# Ethernet.net
KiCad netlist of a schematic drawn in Altium Designer
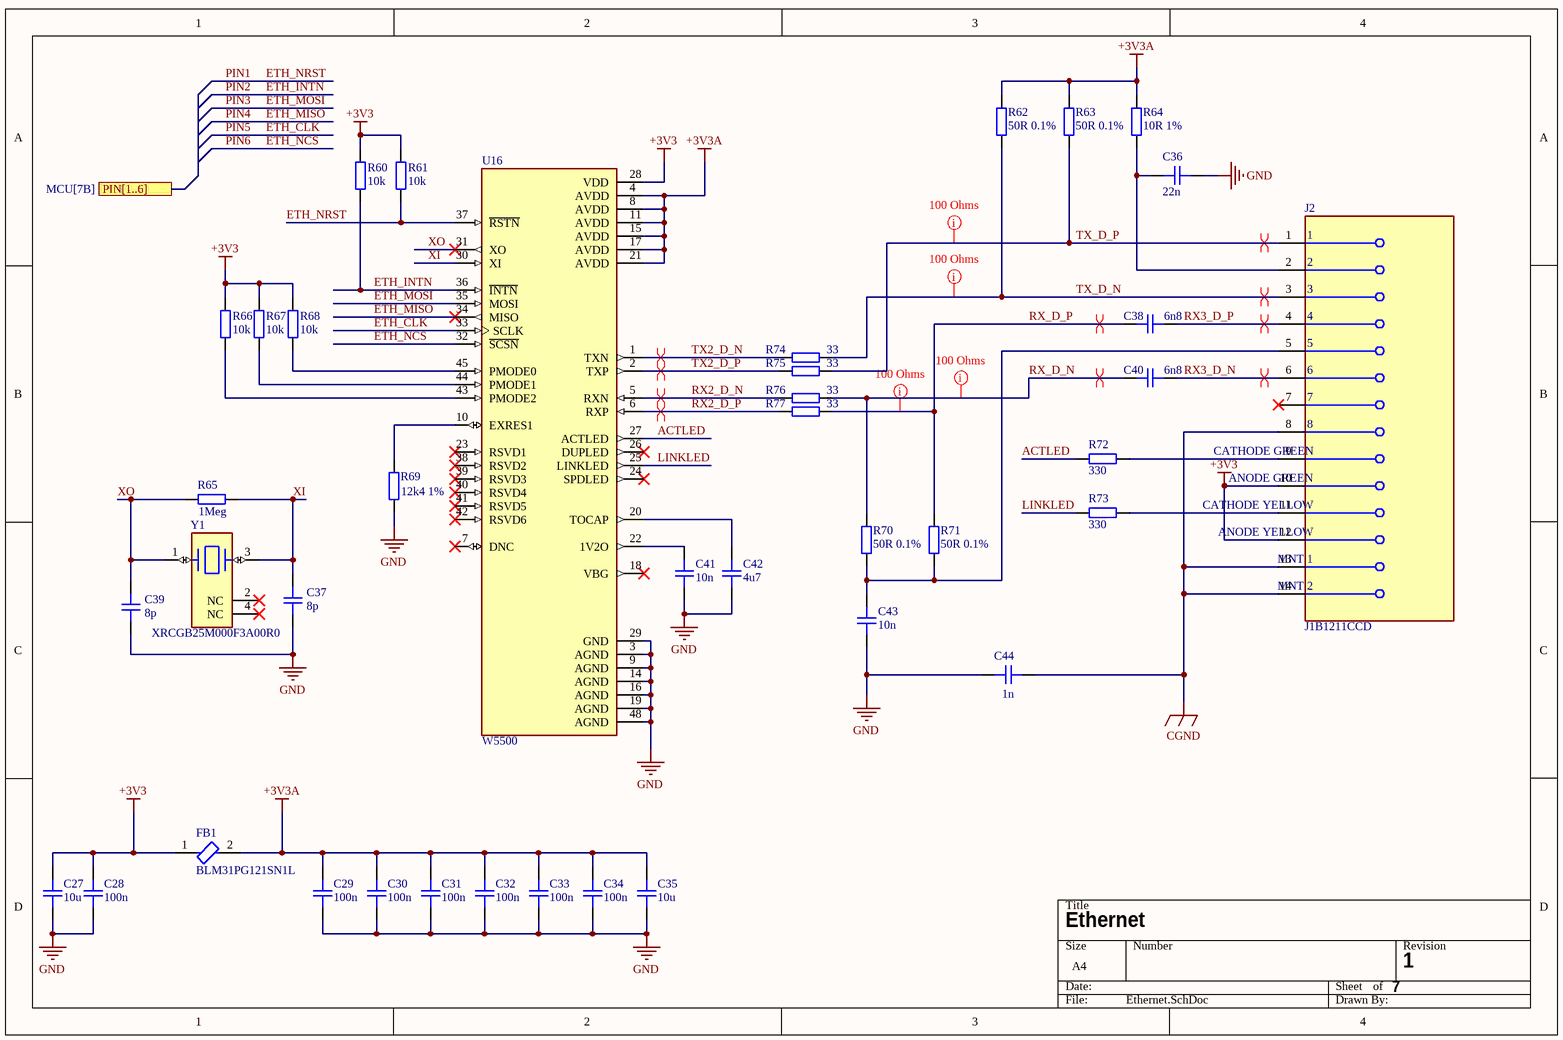
[diagram p0: Ethernet.SchDoc]

(export (version "E")
  (design (tool "Eeschema 10.0.6"))
  (components
    (comp (ref "C27")
      (value "10u")
      (footprint "CAP_0402")
      (description "Capacitor SMD 0402")
      (fields (field (name "Comment") "CL05A106MQ5NUNC"))
      (libsource (lib "Schematic-Lib-PhilsLab") (part "CAP_0402"))
    )
    (comp (ref "C28")
      (value "CL05B104KB54PNC")
      (footprint "CAP_0402")
      (description "Capacitor SMD 0402")
      (fields (field (name "RATING") "100n"))
      (libsource (lib "Schematic-Lib-PhilsLab") (part "CAP_0402"))
    )
    (comp (ref "C29")
      (value "CL05B104KB54PNC")
      (footprint "CAP_0402")
      (description "Capacitor SMD 0402")
      (fields (field (name "RATING") "100n"))
      (libsource (lib "Schematic-Lib-PhilsLab") (part "CAP_0402"))
    )
    (comp (ref "C30")
      (value "CL05B104KB54PNC")
      (footprint "CAP_0402")
      (description "Capacitor SMD 0402")
      (fields (field (name "RATING") "100n"))
      (libsource (lib "Schematic-Lib-PhilsLab") (part "CAP_0402"))
    )
    (comp (ref "C31")
      (value "CL05B104KB54PNC")
      (footprint "CAP_0402")
      (description "Capacitor SMD 0402")
      (fields (field (name "RATING") "100n"))
      (libsource (lib "Schematic-Lib-PhilsLab") (part "CAP_0402"))
    )
    (comp (ref "C32")
      (value "CL05B104KB54PNC")
      (footprint "CAP_0402")
      (description "Capacitor SMD 0402")
      (fields (field (name "RATING") "100n"))
      (libsource (lib "Schematic-Lib-PhilsLab") (part "CAP_0402"))
    )
    (comp (ref "C33")
      (value "CL05B104KB54PNC")
      (footprint "CAP_0402")
      (description "Capacitor SMD 0402")
      (fields (field (name "RATING") "100n"))
      (libsource (lib "Schematic-Lib-PhilsLab") (part "CAP_0402"))
    )
    (comp (ref "C34")
      (value "CL05B104KB54PNC")
      (footprint "CAP_0402")
      (description "Capacitor SMD 0402")
      (fields (field (name "RATING") "100n"))
      (libsource (lib "Schematic-Lib-PhilsLab") (part "CAP_0402"))
    )
    (comp (ref "C35")
      (value "10u")
      (footprint "CAP_0402")
      (description "Capacitor SMD 0402")
      (fields (field (name "Comment") "CL05A106MQ5NUNC"))
      (libsource (lib "Schematic-Lib-PhilsLab") (part "CAP_0402"))
    )
    (comp (ref "C36")
      (value "0402B223K500NT")
      (footprint "CAP_0402")
      (description "Capacitor SMD 0402")
      (fields (field (name "RATING") "22n"))
      (libsource (lib "Schematic-Lib-PhilsLab") (part "CAP_0402"))
    )
    (comp (ref "C37")
      (value "0402CG8R0C500NT")
      (footprint "CAP_0402")
      (description "Capacitor SMD 0402")
      (fields (field (name "RATING") "8p"))
      (libsource (lib "Schematic-Lib-PhilsLab") (part "CAP_0402"))
    )
    (comp (ref "C38")
      (value "0402B682K500NT")
      (footprint "CAP_0402")
      (description "Capacitor SMD 0402")
      (fields (field (name "RATING") "6n8"))
      (libsource (lib "Schematic-Lib-PhilsLab") (part "CAP_0402"))
    )
    (comp (ref "C39")
      (value "0402CG8R0C500NT")
      (footprint "CAP_0402")
      (description "Capacitor SMD 0402")
      (fields (field (name "RATING") "8p"))
      (libsource (lib "Schematic-Lib-PhilsLab") (part "CAP_0402"))
    )
    (comp (ref "C40")
      (value "0402B682K500NT")
      (footprint "CAP_0402")
      (description "Capacitor SMD 0402")
      (fields (field (name "RATING") "6n8"))
      (libsource (lib "Schematic-Lib-PhilsLab") (part "CAP_0402"))
    )
    (comp (ref "C41")
      (value "CL05B103KB5NNNC")
      (footprint "CAP_0402")
      (description "Capacitor SMD 0402")
      (fields (field (name "RATING") "10n"))
      (libsource (lib "Schematic-Lib-PhilsLab") (part "CAP_0402"))
    )
    (comp (ref "C42")
      (value "CL05A475MP5NRNC")
      (footprint "CAP_0402")
      (description "Capacitor SMD 0402")
      (fields (field (name "RATING") "4u7"))
      (libsource (lib "Schematic-Lib-PhilsLab") (part "CAP_0402"))
    )
    (comp (ref "C43")
      (value "CL05B103KB5NNNC")
      (footprint "CAP_0402")
      (description "Capacitor SMD 0402")
      (fields (field (name "RATING") "10n"))
      (libsource (lib "Schematic-Lib-PhilsLab") (part "CAP_0402"))
    )
    (comp (ref "C44")
      (value "CC0402KRX7R0BB102")
      (footprint "CAP_0402")
      (description "Capacitor SMD 0402 100V")
      (fields (field (name "RATING") "1n"))
      (libsource (lib "Schematic-Lib-PhilsLab") (part "CAP_0402"))
    )
    (comp (ref "FB1")
      (value "BLM31PG121SN1L")
      (footprint "FP-BLM31-0_2-t1_1-MFG")
      (description "Chip Ferrite Bead Array, 1206, 120Ω @ 100MHz, 0.02Ω, 25%, 3.5A")
      (fields (field (name "TOLERANCE") "25%"))
      (libsource (lib "Altium Content Vault") (part "5f30dd21d616792df468990f7003faa"))
    )
    (comp (ref "J2")
      (value "J1B1211CCD")
      (footprint "FP-J1B1211CCD-MFG")
      (description "CONN JACK 1PORT 100 BASE-T PCB")
      (libsource (lib "Altium Content Vault") (part "043a9053fb366fe6dc2bf5dbfb72c80"))
    )
    (comp (ref "R60")
      (value "10k")
      (footprint "RES_0402")
      (description "Resistor SMD 0402")
      (fields (field (name "Comment") "0402WGF1002TCE"))
      (libsource (lib "Schematic-Lib-PhilsLab") (part "RES_0402"))
    )
    (comp (ref "R61")
      (value "10k")
      (footprint "RES_0402")
      (description "Resistor SMD 0402")
      (fields (field (name "Comment") "0402WGF1002TCE"))
      (libsource (lib "Schematic-Lib-PhilsLab") (part "RES_0402"))
    )
    (comp (ref "R62")
      (value "RT0402BRE0750RL")
      (footprint "RES_0402")
      (description "Resistor SMD 0402")
      (fields (field (name "RESISTANCE") "50R 0.1%"))
      (libsource (lib "Schematic-Lib-PhilsLab") (part "RES_0402"))
    )
    (comp (ref "R63")
      (value "RT0402BRE0750RL")
      (footprint "RES_0402")
      (description "Resistor SMD 0402")
      (fields (field (name "RESISTANCE") "50R 0.1%"))
      (libsource (lib "Schematic-Lib-PhilsLab") (part "RES_0402"))
    )
    (comp (ref "R64")
      (value "0402WGF100JTCE")
      (footprint "RES_0402")
      (description "Resistor SMD 0402")
      (fields (field (name "PARAMETER") "10R 1%"))
      (libsource (lib "Schematic-Lib-PhilsLab") (part "RES_0402"))
    )
    (comp (ref "R65")
      (value "0402WGF1004TCE")
      (footprint "RES_0402")
      (description "Resistor SMD 0402")
      (fields (field (name "RESISTANCE") "1Meg"))
      (libsource (lib "Schematic-Lib-PhilsLab") (part "RES_0402"))
    )
    (comp (ref "R66")
      (value "10k")
      (footprint "RES_0402")
      (description "Resistor SMD 0402")
      (fields (field (name "Comment") "0402WGF1002TCE"))
      (libsource (lib "Schematic-Lib-PhilsLab") (part "RES_0402"))
    )
    (comp (ref "R67")
      (value "10k")
      (footprint "RES_0402")
      (description "Resistor SMD 0402")
      (fields (field (name "Comment") "0402WGF1002TCE"))
      (libsource (lib "Schematic-Lib-PhilsLab") (part "RES_0402"))
    )
    (comp (ref "R68")
      (value "10k")
      (footprint "RES_0402")
      (description "Resistor SMD 0402")
      (fields (field (name "Comment") "0402WGF1002TCE"))
      (libsource (lib "Schematic-Lib-PhilsLab") (part "RES_0402"))
    )
    (comp (ref "R69")
      (value "0402WGF1242TCE")
      (footprint "RES_0402")
      (description "Resistor SMD 0402")
      (fields (field (name "RESISTANCE") "12k4 1%"))
      (libsource (lib "Schematic-Lib-PhilsLab") (part "RES_0402"))
    )
    (comp (ref "R70")
      (value "RT0402BRE0750RL")
      (footprint "RES_0402")
      (description "Resistor SMD 0402")
      (fields (field (name "RESISTANCE") "50R 0.1%"))
      (libsource (lib "Schematic-Lib-PhilsLab") (part "RES_0402"))
    )
    (comp (ref "R71")
      (value "RT0402BRE0750RL")
      (footprint "RES_0402")
      (description "Resistor SMD 0402")
      (fields (field (name "RESISTANCE") "50R 0.1%"))
      (libsource (lib "Schematic-Lib-PhilsLab") (part "RES_0402"))
    )
    (comp (ref "R72")
      (value "0402WGF3300TCE")
      (footprint "RES_0402")
      (description "Resistor SMD 0402")
      (fields (field (name "RESISTANCE") "330"))
      (libsource (lib "Schematic-Lib-PhilsLab") (part "RES_0402"))
    )
    (comp (ref "R73")
      (value "0402WGF3300TCE")
      (footprint "RES_0402")
      (description "Resistor SMD 0402")
      (fields (field (name "RESISTANCE") "330"))
      (libsource (lib "Schematic-Lib-PhilsLab") (part "RES_0402"))
    )
    (comp (ref "R74")
      (value "0402WGF330JTCE")
      (footprint "RES_0402")
      (description "Resistor SMD 0402")
      (fields (field (name "RESISTANCE") "33"))
      (libsource (lib "Schematic-Lib-PhilsLab") (part "RES_0402"))
    )
    (comp (ref "R75")
      (value "0402WGF330JTCE")
      (footprint "RES_0402")
      (description "Resistor SMD 0402")
      (fields (field (name "RESISTANCE") "33"))
      (libsource (lib "Schematic-Lib-PhilsLab") (part "RES_0402"))
    )
    (comp (ref "R76")
      (value "0402WGF330JTCE")
      (footprint "RES_0402")
      (description "Resistor SMD 0402")
      (fields (field (name "RESISTANCE") "33"))
      (libsource (lib "Schematic-Lib-PhilsLab") (part "RES_0402"))
    )
    (comp (ref "R77")
      (value "0402WGF330JTCE")
      (footprint "RES_0402")
      (description "Resistor SMD 0402")
      (fields (field (name "RESISTANCE") "33"))
      (libsource (lib "Schematic-Lib-PhilsLab") (part "RES_0402"))
    )
    (comp (ref "U16")
      (value "W5500")
      (footprint "QFP50P900X900X160-48N:QFP50P900X900X160-48N")
      (description "Hardwired TCP/IP embedded Ethernet controller")
      (libsource (lib "W5500") (part "W5500"))
    )
    (comp (ref "Y1")
      (value "XRCGB25M000F3A00R0")
      (footprint "FP-XRCGB-MFG")
      (description "CRYSTAL 25.0000MHZ 6PF SMD")
      (libsource (lib "Altium Content Vault") (part "a98f302eae8e461f85c3fa51db172f8"))
    )
  )
  (nets
    (net (code "1") (name "+3V3") (class "Default")
      (node (ref "C27") (pin "1") (pinfunction "1_1") (pintype "passive"))
      (node (ref "C28") (pin "2") (pinfunction "2_2") (pintype "passive"))
      (node (ref "FB1") (pin "1") (pinfunction "1_1") (pintype "passive"))
      (node (ref "J2") (pin "10") (pinfunction "ANODE_GREEN_10") (pintype "passive"))
      (node (ref "J2") (pin "12") (pinfunction "ANODE_YELLOW_12") (pintype "passive"))
      (node (ref "R60") (pin "2") (pinfunction "2_2") (pintype "passive"))
      (node (ref "R61") (pin "2") (pinfunction "2_2") (pintype "passive"))
      (node (ref "R66") (pin "2") (pinfunction "2_2") (pintype "passive"))
      (node (ref "R67") (pin "2") (pinfunction "2_2") (pintype "passive"))
      (node (ref "R68") (pin "2") (pinfunction "2_2") (pintype "passive"))
      (node (ref "U16") (pin "28") (pinfunction "VDD_28") (pintype "power_in"))
    )
    (net (code "2") (name "+3V3A") (class "Default")
      (node (ref "C29") (pin "1") (pinfunction "1_1") (pintype "passive"))
      (node (ref "C30") (pin "1") (pinfunction "1_1") (pintype "passive"))
      (node (ref "C31") (pin "1") (pinfunction "1_1") (pintype "passive"))
      (node (ref "C32") (pin "1") (pinfunction "1_1") (pintype "passive"))
      (node (ref "C33") (pin "1") (pinfunction "1_1") (pintype "passive"))
      (node (ref "C34") (pin "1") (pinfunction "1_1") (pintype "passive"))
      (node (ref "C35") (pin "1") (pinfunction "1_1") (pintype "passive"))
      (node (ref "FB1") (pin "2") (pinfunction "2_2") (pintype "passive"))
      (node (ref "R62") (pin "2") (pinfunction "2_2") (pintype "passive"))
      (node (ref "R63") (pin "2") (pinfunction "2_2") (pintype "passive"))
      (node (ref "R64") (pin "2") (pinfunction "2_2") (pintype "passive"))
      (node (ref "U16") (pin "11") (pinfunction "AVDD_11") (pintype "power_in"))
      (node (ref "U16") (pin "15") (pinfunction "AVDD_15") (pintype "power_in"))
      (node (ref "U16") (pin "17") (pinfunction "AVDD_17") (pintype "power_in"))
      (node (ref "U16") (pin "21") (pinfunction "AVDD_21") (pintype "power_in"))
      (node (ref "U16") (pin "4") (pinfunction "AVDD_4") (pintype "power_in"))
      (node (ref "U16") (pin "8") (pinfunction "AVDD_8") (pintype "power_in"))
    )
    (net (code "3") (name "/ACTLED") (class "Default")
      (node (ref "R72") (pin "2") (pinfunction "2_2") (pintype "passive"))
      (node (ref "U16") (pin "27") (pinfunction "ACTLED_27") (pintype "output"))
    )
    (net (code "4") (name "/LINKLED") (class "Default")
      (node (ref "R73") (pin "2") (pinfunction "2_2") (pintype "passive"))
      (node (ref "U16") (pin "25") (pinfunction "LINKLED_25") (pintype "output"))
    )
    (net (code "5") (name "/PIN1") (class "Default")
      (node (ref "R61") (pin "1") (pinfunction "1_1") (pintype "passive"))
      (node (ref "U16") (pin "37") (pinfunction "~{RSTN}_37") (pintype "input"))
    )
    (net (code "6") (name "/PIN2") (class "Default")
      (node (ref "R60") (pin "1") (pinfunction "1_1") (pintype "passive"))
      (node (ref "U16") (pin "36") (pinfunction "~{INTN}_36") (pintype "input"))
    )
    (net (code "7") (name "/PIN3") (class "Default")
      (node (ref "U16") (pin "35") (pinfunction "MOSI_35") (pintype "input"))
    )
    (net (code "8") (name "/PIN4") (class "Default")
      (node (ref "U16") (pin "34") (pinfunction "MISO_34") (pintype "output+no_connect"))
    )
    (net (code "9") (name "/PIN5") (class "Default")
      (node (ref "U16") (pin "33") (pinfunction "SCLK_33") (pintype "input"))
    )
    (net (code "10") (name "/PIN6") (class "Default")
      (node (ref "U16") (pin "32") (pinfunction "~{SCSN}_32") (pintype "input"))
    )
    (net (code "12") (name "/RX2_D_N") (class "Default")
      (node (ref "R76") (pin "1") (pinfunction "1_1") (pintype "passive"))
      (node (ref "U16") (pin "5") (pinfunction "RXN_5") (pintype "input"))
    )
    (net (code "13") (name "/RX2_D_P") (class "Default")
      (node (ref "R77") (pin "1") (pinfunction "1_1") (pintype "passive"))
      (node (ref "U16") (pin "6") (pinfunction "RXP_6") (pintype "input"))
    )
    (net (code "14") (name "/RX3_D_N") (class "Default")
      (node (ref "C40") (pin "1") (pinfunction "1_1") (pintype "passive"))
      (node (ref "J2") (pin "6") (pinfunction "6_6") (pintype "passive"))
    )
    (net (code "15") (name "/RX3_D_P") (class "Default")
      (node (ref "C38") (pin "1") (pinfunction "1_1") (pintype "passive"))
      (node (ref "J2") (pin "4") (pinfunction "4_4") (pintype "passive"))
    )
    (net (code "16") (name "/RX_D_N") (class "Default")
      (node (ref "C40") (pin "2") (pinfunction "2_2") (pintype "passive"))
      (node (ref "R70") (pin "2") (pinfunction "2_2") (pintype "passive"))
      (node (ref "R76") (pin "2") (pinfunction "2_2") (pintype "passive"))
    )
    (net (code "17") (name "/RX_D_P") (class "Default")
      (node (ref "C38") (pin "2") (pinfunction "2_2") (pintype "passive"))
      (node (ref "R71") (pin "2") (pinfunction "2_2") (pintype "passive"))
      (node (ref "R77") (pin "2") (pinfunction "2_2") (pintype "passive"))
    )
    (net (code "18") (name "/TX2_D_N") (class "Default")
      (node (ref "R74") (pin "1") (pinfunction "1_1") (pintype "passive"))
      (node (ref "U16") (pin "1") (pinfunction "TXN_1") (pintype "output"))
    )
    (net (code "19") (name "/TX2_D_P") (class "Default")
      (node (ref "R75") (pin "1") (pinfunction "1_1") (pintype "passive"))
      (node (ref "U16") (pin "2") (pinfunction "TXP_2") (pintype "output"))
    )
    (net (code "20") (name "/TX_D_N") (class "Default")
      (node (ref "J2") (pin "3") (pinfunction "3_3") (pintype "passive"))
      (node (ref "R62") (pin "1") (pinfunction "1_1") (pintype "passive"))
      (node (ref "R74") (pin "2") (pinfunction "2_2") (pintype "passive"))
    )
    (net (code "21") (name "/TX_D_P") (class "Default")
      (node (ref "J2") (pin "1") (pinfunction "1_1") (pintype "passive"))
      (node (ref "R63") (pin "1") (pinfunction "1_1") (pintype "passive"))
      (node (ref "R75") (pin "2") (pinfunction "2_2") (pintype "passive"))
    )
    (net (code "22") (name "/XI") (class "Default")
      (node (ref "C37") (pin "2") (pinfunction "2_2") (pintype "passive"))
      (node (ref "R65") (pin "2") (pinfunction "2_2") (pintype "passive"))
      (node (ref "U16") (pin "30") (pinfunction "XI_30") (pintype "input"))
      (node (ref "Y1") (pin "3") (pinfunction "Input/Output_3") (pintype "bidirectional"))
    )
    (net (code "23") (name "/XO") (class "Default")
      (node (ref "C39") (pin "2") (pinfunction "2_2") (pintype "passive"))
      (node (ref "R65") (pin "1") (pinfunction "1_1") (pintype "passive"))
      (node (ref "U16") (pin "31") (pinfunction "XO_31") (pintype "output"))
      (node (ref "Y1") (pin "1") (pinfunction "Input/Output_1") (pintype "bidirectional"))
    )
    (net (code "24") (name "CGND") (class "Default")
      (node (ref "C44") (pin "2") (pinfunction "2_2") (pintype "passive"))
      (node (ref "J2") (pin "13") (pinfunction "MNT_1_13") (pintype "passive"))
      (node (ref "J2") (pin "14") (pinfunction "MNT_2_14") (pintype "passive"))
      (node (ref "J2") (pin "8") (pinfunction "8_8") (pintype "passive"))
    )
    (net (code "25") (name "GND") (class "Default")
      (node (ref "C27") (pin "2") (pinfunction "2_2") (pintype "passive"))
      (node (ref "C28") (pin "1") (pinfunction "1_1") (pintype "passive"))
      (node (ref "C29") (pin "2") (pinfunction "2_2") (pintype "passive"))
      (node (ref "C30") (pin "2") (pinfunction "2_2") (pintype "passive"))
      (node (ref "C31") (pin "2") (pinfunction "2_2") (pintype "passive"))
      (node (ref "C32") (pin "2") (pinfunction "2_2") (pintype "passive"))
      (node (ref "C33") (pin "2") (pinfunction "2_2") (pintype "passive"))
      (node (ref "C34") (pin "2") (pinfunction "2_2") (pintype "passive"))
      (node (ref "C35") (pin "2") (pinfunction "2_2") (pintype "passive"))
      (node (ref "C36") (pin "1") (pinfunction "1_1") (pintype "passive"))
      (node (ref "C37") (pin "1") (pinfunction "1_1") (pintype "passive"))
      (node (ref "C39") (pin "1") (pinfunction "1_1") (pintype "passive"))
      (node (ref "C41") (pin "1") (pinfunction "1_1") (pintype "passive"))
      (node (ref "C42") (pin "1") (pinfunction "1_1") (pintype "passive"))
      (node (ref "C43") (pin "1") (pinfunction "1_1") (pintype "passive"))
      (node (ref "C44") (pin "1") (pinfunction "1_1") (pintype "passive"))
      (node (ref "R69") (pin "1") (pinfunction "1_1") (pintype "passive"))
      (node (ref "U16") (pin "14") (pinfunction "AGND_14") (pintype "power_in"))
      (node (ref "U16") (pin "16") (pinfunction "AGND_16") (pintype "power_in"))
      (node (ref "U16") (pin "19") (pinfunction "AGND_19") (pintype "power_in"))
      (node (ref "U16") (pin "29") (pinfunction "GND_29") (pintype "passive"))
      (node (ref "U16") (pin "3") (pinfunction "AGND_3") (pintype "power_in"))
      (node (ref "U16") (pin "48") (pinfunction "AGND_48") (pintype "power_in"))
      (node (ref "U16") (pin "9") (pinfunction "AGND_9") (pintype "power_in"))
    )
    (net (code "26") (name "Net-(C36-Pad2)") (class "Default")
      (node (ref "C36") (pin "2") (pinfunction "2_2") (pintype "passive"))
      (node (ref "J2") (pin "2") (pinfunction "2_2") (pintype "passive"))
      (node (ref "R64") (pin "1") (pinfunction "1_1") (pintype "passive"))
    )
    (net (code "27") (name "Net-(C43-Pad2)") (class "Default")
      (node (ref "C43") (pin "2") (pinfunction "2_2") (pintype "passive"))
      (node (ref "J2") (pin "5") (pinfunction "5_5") (pintype "passive"))
      (node (ref "R70") (pin "1") (pinfunction "1_1") (pintype "passive"))
      (node (ref "R71") (pin "1") (pinfunction "1_1") (pintype "passive"))
    )
    (net (code "28") (name "Net-(J2-CATHODE_GREEN)") (class "Default")
      (node (ref "J2") (pin "9") (pinfunction "CATHODE_GREEN_9") (pintype "passive"))
      (node (ref "R72") (pin "1") (pinfunction "1_1") (pintype "passive"))
    )
    (net (code "29") (name "Net-(J2-CATHODE_YELLOW)") (class "Default")
      (node (ref "J2") (pin "11") (pinfunction "CATHODE_YELLOW_11") (pintype "passive"))
      (node (ref "R73") (pin "1") (pinfunction "1_1") (pintype "passive"))
    )
    (net (code "30") (name "Net-(U16-1V2O)") (class "Default")
      (node (ref "C41") (pin "2") (pinfunction "2_2") (pintype "passive"))
      (node (ref "U16") (pin "22") (pinfunction "1V2O_22") (pintype "output"))
    )
    (net (code "31") (name "Net-(U16-EXRES1)") (class "Default")
      (node (ref "R69") (pin "2") (pinfunction "2_2") (pintype "passive"))
      (node (ref "U16") (pin "10") (pinfunction "EXRES1_10") (pintype "bidirectional"))
    )
    (net (code "32") (name "Net-(U16-PMODE0)") (class "Default")
      (node (ref "R68") (pin "1") (pinfunction "1_1") (pintype "passive"))
      (node (ref "U16") (pin "45") (pinfunction "PMODE0_45") (pintype "input"))
    )
    (net (code "33") (name "Net-(U16-PMODE1)") (class "Default")
      (node (ref "R67") (pin "1") (pinfunction "1_1") (pintype "passive"))
      (node (ref "U16") (pin "44") (pinfunction "PMODE1_44") (pintype "input"))
    )
    (net (code "34") (name "Net-(U16-PMODE2)") (class "Default")
      (node (ref "R66") (pin "1") (pinfunction "1_1") (pintype "passive"))
      (node (ref "U16") (pin "43") (pinfunction "PMODE2_43") (pintype "input"))
    )
    (net (code "35") (name "Net-(U16-TOCAP)") (class "Default")
      (node (ref "C42") (pin "2") (pinfunction "2_2") (pintype "passive"))
      (node (ref "U16") (pin "20") (pinfunction "TOCAP_20") (pintype "output"))
    )
    (net (code "36") (name "unconnected-(J2-Pad7)") (class "Default")
      (node (ref "J2") (pin "7") (pinfunction "7_7") (pintype "passive+no_connect"))
    )
    (net (code "37") (name "unconnected-(U16-DNC-Pad7)") (class "Default")
      (node (ref "U16") (pin "7") (pinfunction "DNC_7") (pintype "bidirectional+no_connect"))
    )
    (net (code "38") (name "unconnected-(U16-DUPLED-Pad26)") (class "Default")
      (node (ref "U16") (pin "26") (pinfunction "DUPLED_26") (pintype "output+no_connect"))
    )
    (net (code "39") (name "unconnected-(U16-RSVD1-Pad23)") (class "Default")
      (node (ref "U16") (pin "23") (pinfunction "RSVD1_23") (pintype "input+no_connect"))
    )
    (net (code "40") (name "unconnected-(U16-RSVD2-Pad38)") (class "Default")
      (node (ref "U16") (pin "38") (pinfunction "RSVD2_38") (pintype "input+no_connect"))
    )
    (net (code "41") (name "unconnected-(U16-RSVD3-Pad39)") (class "Default")
      (node (ref "U16") (pin "39") (pinfunction "RSVD3_39") (pintype "input+no_connect"))
    )
    (net (code "42") (name "unconnected-(U16-RSVD4-Pad40)") (class "Default")
      (node (ref "U16") (pin "40") (pinfunction "RSVD4_40") (pintype "input+no_connect"))
    )
    (net (code "43") (name "unconnected-(U16-RSVD5-Pad41)") (class "Default")
      (node (ref "U16") (pin "41") (pinfunction "RSVD5_41") (pintype "input+no_connect"))
    )
    (net (code "44") (name "unconnected-(U16-RSVD6-Pad42)") (class "Default")
      (node (ref "U16") (pin "42") (pinfunction "RSVD6_42") (pintype "input+no_connect"))
    )
    (net (code "45") (name "unconnected-(U16-SPDLED-Pad24)") (class "Default")
      (node (ref "U16") (pin "24") (pinfunction "SPDLED_24") (pintype "output+no_connect"))
    )
    (net (code "46") (name "unconnected-(U16-VBG-Pad18)") (class "Default")
      (node (ref "U16") (pin "18") (pinfunction "VBG_18") (pintype "output+no_connect"))
    )
    (net (code "47") (name "unconnected-(Y1-NC-Pad2)") (class "Default")
      (node (ref "Y1") (pin "2") (pinfunction "NC_2") (pintype "passive+no_connect"))
    )
    (net (code "48") (name "unconnected-(Y1-NC-Pad4)") (class "Default")
      (node (ref "Y1") (pin "4") (pinfunction "NC_4") (pintype "passive+no_connect"))
    )
  )
)
